# PLP-200.net
KiCad netlist of a schematic drawn in EAGLE
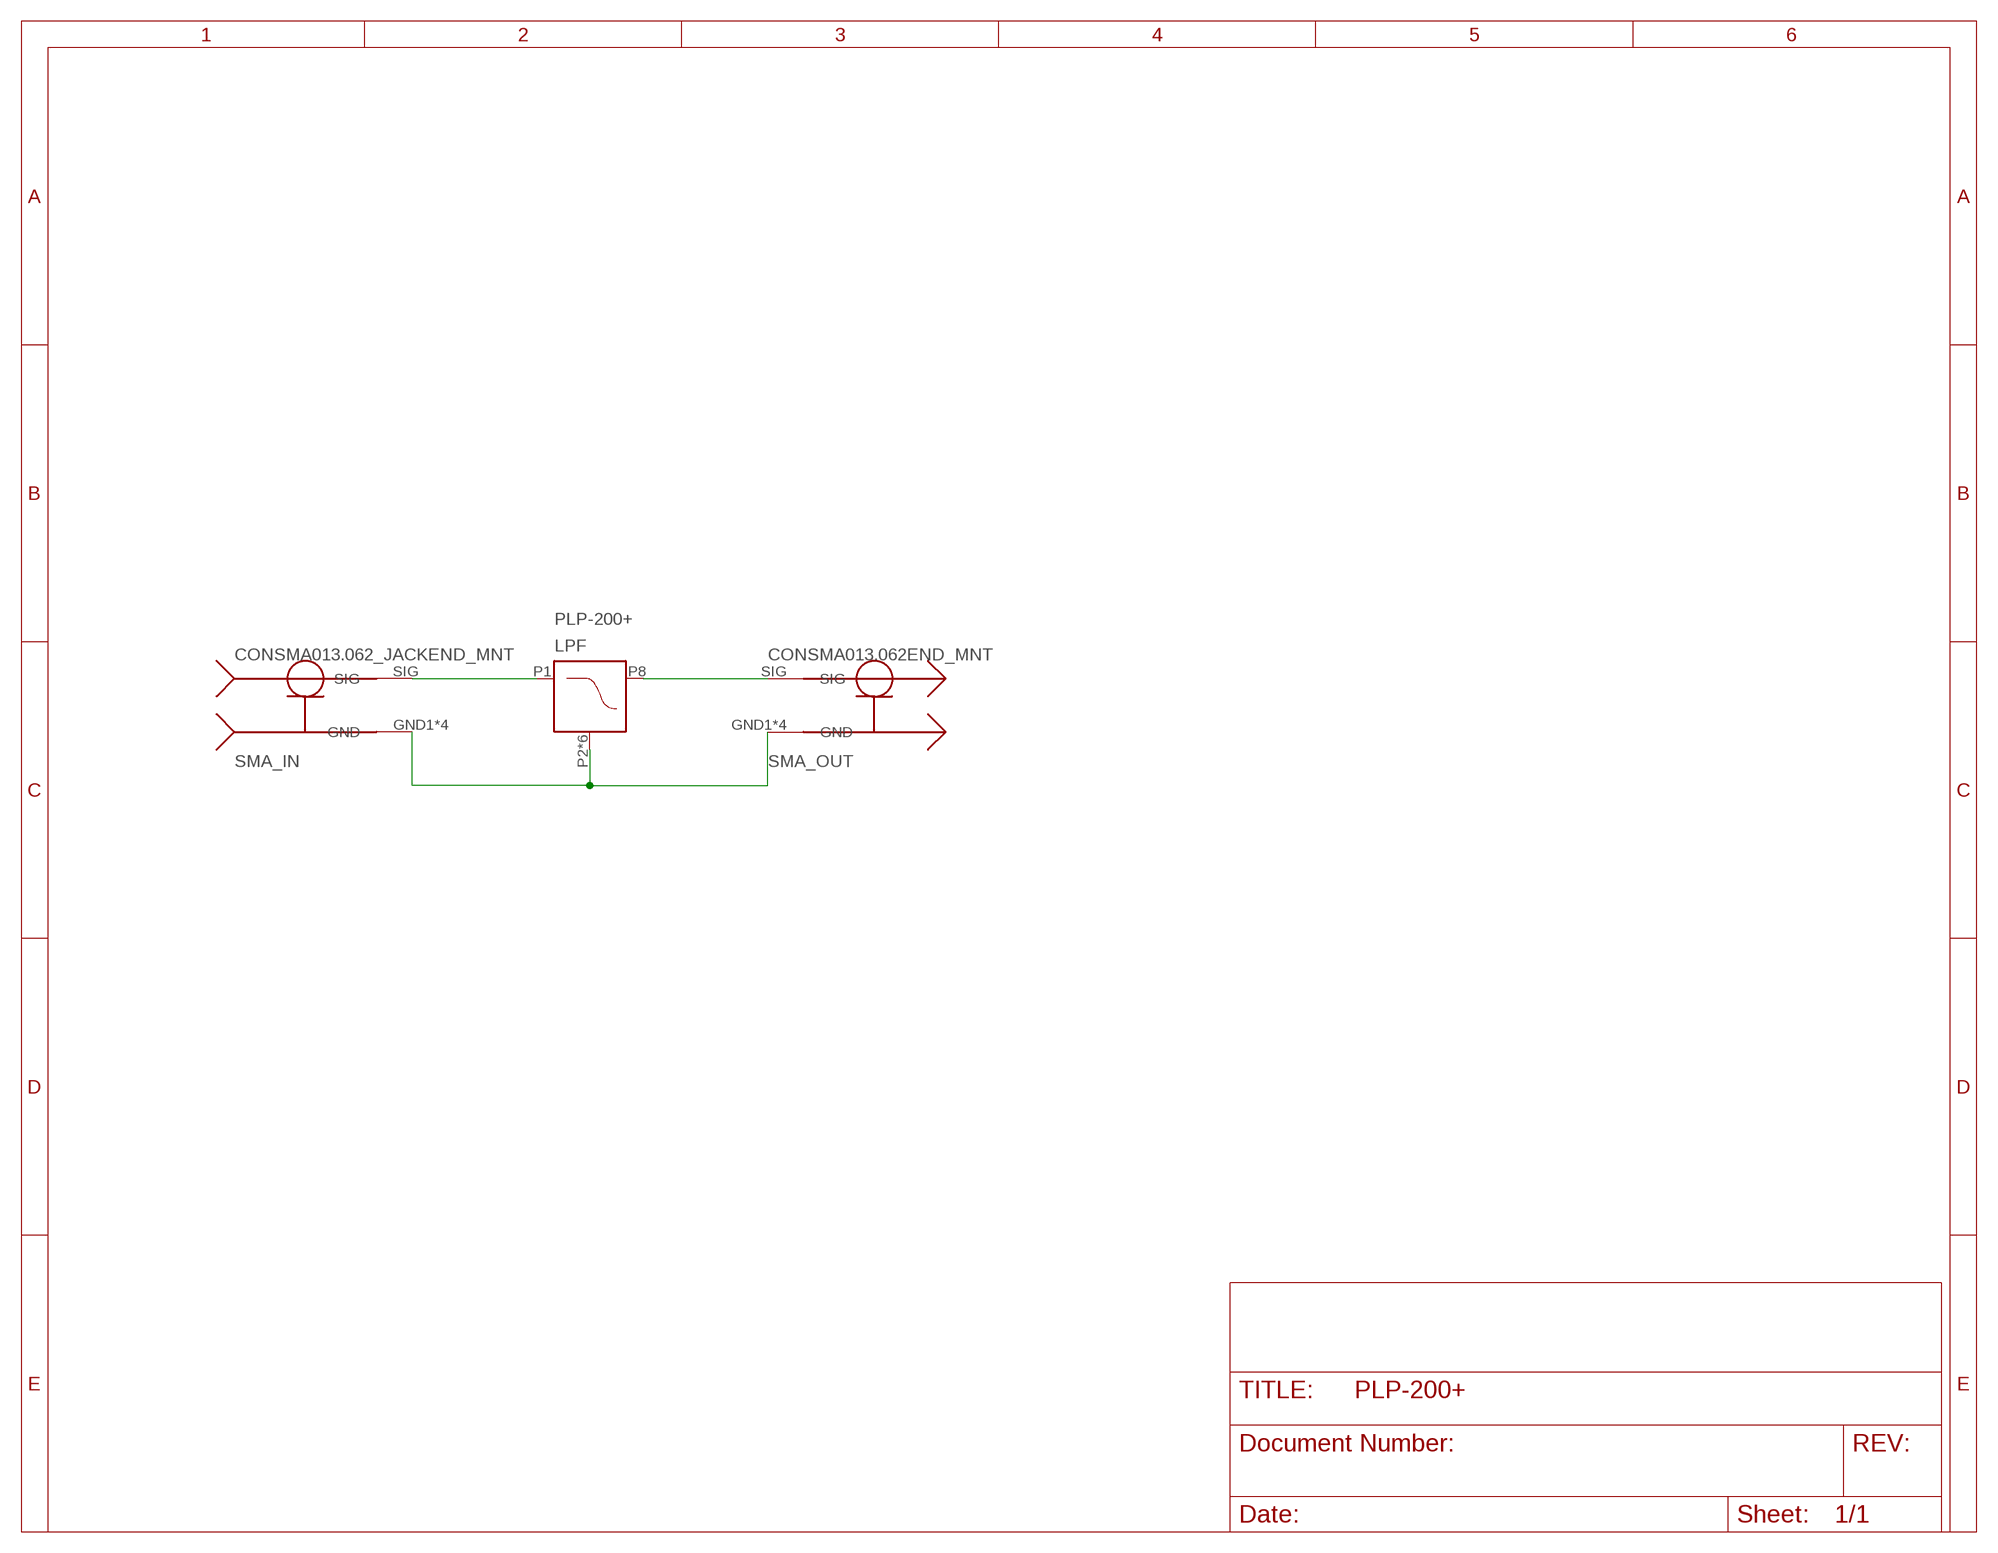
[diagram p0: schematic, sheet 1]

(export (version "E")
  (design (tool "Eeschema 10.0.6"))
  (components
    (comp (ref "LPF")
      (value "PLP-200+")
      (footprint "eagle-import:A01")
      (libsource (lib "eagle-import") (part "PLP-200+"))
    )
    (comp (ref "SMA_IN")
      (value "CONSMA013.062_JACKEND_MNT")
      (footprint "eagle-import:SMA_EDGE_MNT")
      (libsource (lib "eagle-import") (part "CONSMA013.062_JACKEND_MNT"))
    )
    (comp (ref "SMA_OUT")
      (value "CONSMA013.062END_MNT")
      (footprint "eagle-import:SMA_EDGE_MNT")
      (libsource (lib "eagle-import") (part "CONSMA013.062END_MNT"))
    )
  )
  (nets
    (net (code "1") (name "Net-(LPF-GND-PadP2)") (class "Default")
      (node (ref "LPF") (pin "P2") (pinfunction "GND_P2") (pintype "bidirectional"))
      (node (ref "LPF") (pin "P3") (pinfunction "GND_P3") (pintype "bidirectional"))
      (node (ref "LPF") (pin "P4") (pinfunction "GND_P4") (pintype "bidirectional"))
      (node (ref "LPF") (pin "P5") (pinfunction "GND_P5") (pintype "bidirectional"))
      (node (ref "LPF") (pin "P6") (pinfunction "GND_P6") (pintype "bidirectional"))
      (node (ref "LPF") (pin "P7") (pinfunction "GND_P7") (pintype "bidirectional"))
      (node (ref "SMA_IN") (pin "GND1") (pinfunction "GND_GND1") (pintype "bidirectional"))
      (node (ref "SMA_IN") (pin "GND2") (pinfunction "GND_GND2") (pintype "bidirectional"))
      (node (ref "SMA_IN") (pin "GND3") (pinfunction "GND_GND3") (pintype "bidirectional"))
      (node (ref "SMA_IN") (pin "GND4") (pinfunction "GND_GND4") (pintype "bidirectional"))
      (node (ref "SMA_OUT") (pin "GND1") (pinfunction "GND_GND1") (pintype "bidirectional"))
      (node (ref "SMA_OUT") (pin "GND2") (pinfunction "GND_GND2") (pintype "bidirectional"))
      (node (ref "SMA_OUT") (pin "GND3") (pinfunction "GND_GND3") (pintype "bidirectional"))
      (node (ref "SMA_OUT") (pin "GND4") (pinfunction "GND_GND4") (pintype "bidirectional"))
    )
    (net (code "2") (name "Net-(LPF-RF_IN)") (class "Default")
      (node (ref "LPF") (pin "P1") (pinfunction "RF_IN_P1") (pintype "input"))
      (node (ref "SMA_IN") (pin "SIG") (pinfunction "SIG_SIG") (pintype "bidirectional"))
    )
    (net (code "3") (name "Net-(LPF-RF_OUT)") (class "Default")
      (node (ref "LPF") (pin "P8") (pinfunction "RF_OUT_P8") (pintype "output"))
      (node (ref "SMA_OUT") (pin "SIG") (pinfunction "SIG_SIG") (pintype "bidirectional"))
    )
  )
)
